# SP2.net
KiCad netlist of a schematic drawn in EAGLE
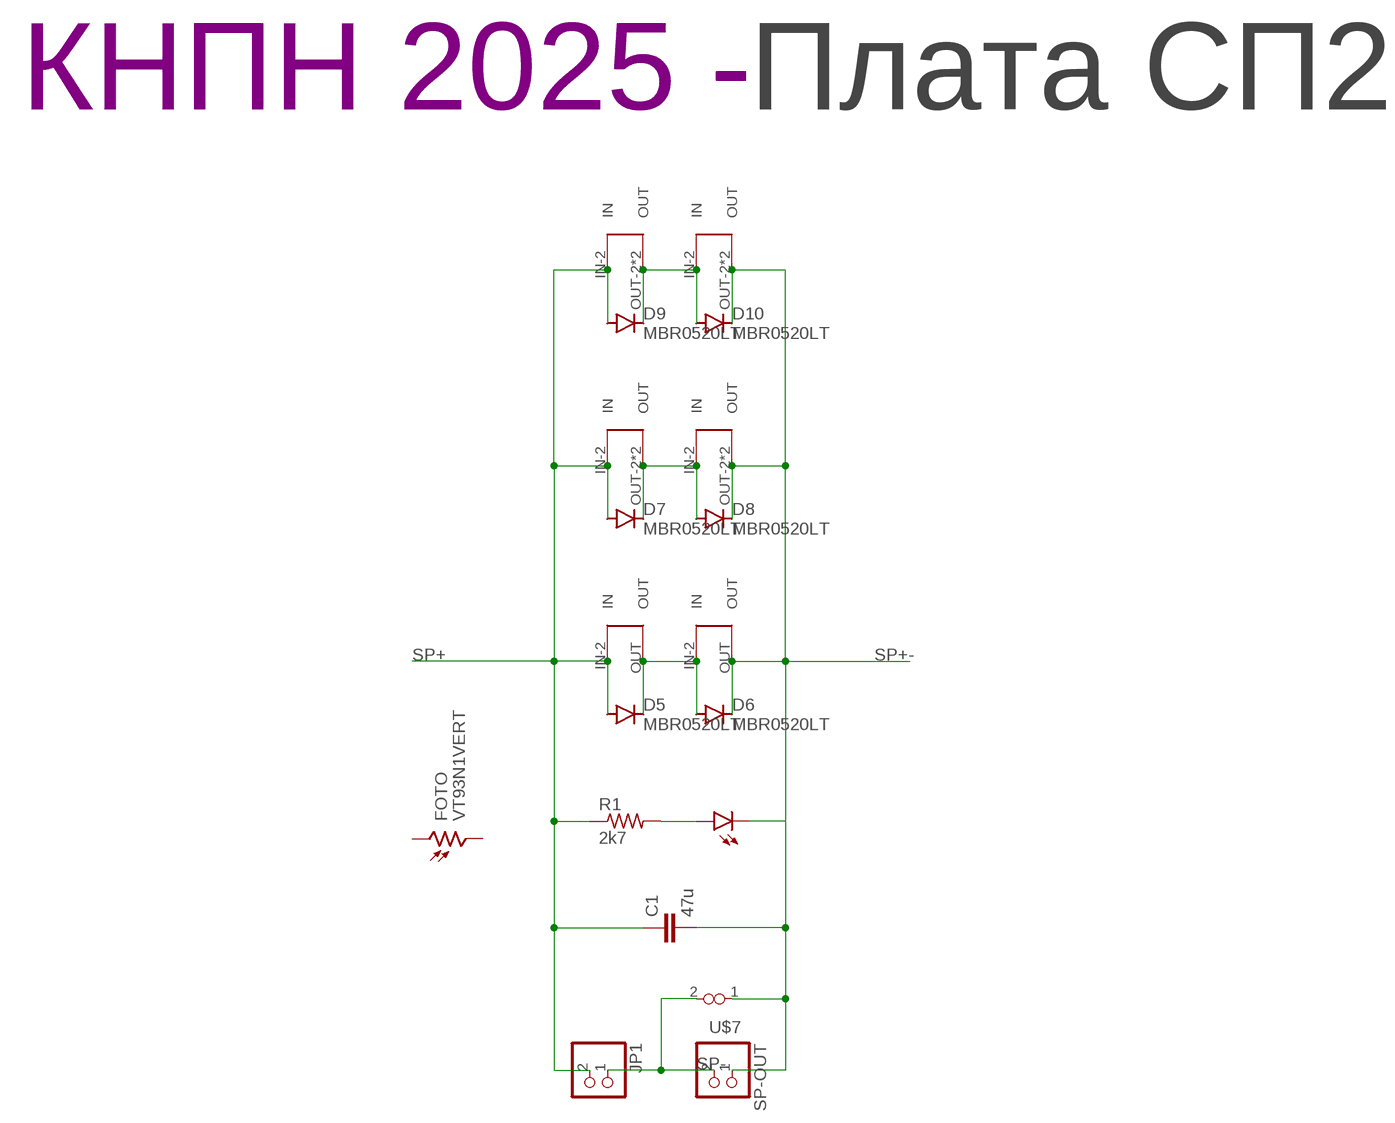
[diagram p0: schematic, sheet 1]

(export (version "E")
  (design (tool "Eeschema 10.0.6"))
  (components
    (comp (ref "C1")
      (value "47u")
      (footprint "eagle-import:C1210")
      (libsource (lib "eagle-import") (part "C-EUC1210"))
    )
    (comp (ref "D5")
      (value "MBR0520LT")
      (footprint "eagle-import:SOD123")
      (libsource (lib "eagle-import") (part "MBR0520LT"))
    )
    (comp (ref "D6")
      (value "MBR0520LT")
      (footprint "eagle-import:SOD123")
      (libsource (lib "eagle-import") (part "MBR0520LT"))
    )
    (comp (ref "D7")
      (value "MBR0520LT")
      (footprint "eagle-import:SOD123")
      (libsource (lib "eagle-import") (part "MBR0520LT"))
    )
    (comp (ref "D8")
      (value "MBR0520LT")
      (footprint "eagle-import:SOD123")
      (libsource (lib "eagle-import") (part "MBR0520LT"))
    )
    (comp (ref "D9")
      (value "MBR0520LT")
      (footprint "eagle-import:SOD123")
      (libsource (lib "eagle-import") (part "MBR0520LT"))
    )
    (comp (ref "D10")
      (value "MBR0520LT")
      (footprint "eagle-import:SOD123")
      (libsource (lib "eagle-import") (part "MBR0520LT"))
    )
    (comp (ref "FOTO")
      (value "VT93N1VERT")
      (footprint "eagle-import:VT93N1-VERT")
      (libsource (lib "eagle-import") (part "VT93N1VERT"))
    )
    (comp (ref "JP1")
      (value "PINHD-1X2")
      (footprint "eagle-import:1X02")
      (libsource (lib "eagle-import") (part "PINHD-1X2"))
    )
    (comp (ref "PWR")
      (value "LEDCHIP-LED0603")
      (footprint "eagle-import:CHIP-LED0603")
      (libsource (lib "eagle-import") (part "LEDCHIP-LED0603"))
    )
    (comp (ref "R1")
      (value "2k7")
      (footprint "eagle-import:R0603")
      (libsource (lib "eagle-import") (part "R-US_R0603"))
    )
    (comp (ref "SP-OUT")
      (value "PINHD-1X2")
      (footprint "eagle-import:1X02")
      (libsource (lib "eagle-import") (part "PINHD-1X2"))
    )
    (comp (ref "U$1")
      (value "Плата СП2")
      (footprint "eagle-import:LOGO")
      (libsource (lib "eagle-import") (part "LOGOPCB-{dblquote}{dblquote}"))
    )
    (comp (ref "U$5")
      (value "SOLAR-2_1")
      (footprint "eagle-import:SOLAR_1-2")
      (libsource (lib "eagle-import") (part "SOLAR-2_1"))
    )
    (comp (ref "U$6")
      (value "SOLAR-2_1")
      (footprint "eagle-import:SOLAR_1-2")
      (libsource (lib "eagle-import") (part "SOLAR-2_1"))
    )
    (comp (ref "U$7")
      (value "VIAS-CONNECT")
      (footprint "eagle-import:VIAS-CONNECT")
      (libsource (lib "eagle-import") (part "VIAS-CONNECT"))
    )
    (comp (ref "U$8")
      (value "SOLAR-2_0")
      (footprint "eagle-import:SOLAR_0-2")
      (libsource (lib "eagle-import") (part "SOLAR-2_0"))
    )
    (comp (ref "U$9")
      (value "SOLAR-2_0")
      (footprint "eagle-import:SOLAR_0-2")
      (libsource (lib "eagle-import") (part "SOLAR-2_0"))
    )
    (comp (ref "U$10")
      (value "SOLAR-2_0")
      (footprint "eagle-import:SOLAR_0-2")
      (libsource (lib "eagle-import") (part "SOLAR-2_0"))
    )
    (comp (ref "U$11")
      (value "SOLAR-2_0")
      (footprint "eagle-import:SOLAR_0-2")
      (libsource (lib "eagle-import") (part "SOLAR-2_0"))
    )
  )
  (nets
    (net (code "1") (name "/SP+") (class "Default")
      (node (ref "C1") (pin "1") (pinfunction "1_1") (pintype "passive"))
      (node (ref "D5") (pin "A") (pinfunction "A_A") (pintype "passive"))
      (node (ref "D7") (pin "A") (pinfunction "A_A") (pintype "passive"))
      (node (ref "D9") (pin "A") (pinfunction "A_A") (pintype "passive"))
      (node (ref "JP1") (pin "2") (pinfunction "2_2") (pintype "passive"))
      (node (ref "R1") (pin "1") (pinfunction "1_1") (pintype "passive"))
      (node (ref "U$10") (pin "IN-2") (pinfunction "IN_IN-2") (pintype "bidirectional"))
      (node (ref "U$5") (pin "IN-2") (pinfunction "IN_IN-2") (pintype "bidirectional"))
      (node (ref "U$8") (pin "IN-2") (pinfunction "IN_IN-2") (pintype "bidirectional"))
    )
    (net (code "2") (name "/SP+-") (class "Default")
      (node (ref "C1") (pin "2") (pinfunction "2_2") (pintype "passive"))
      (node (ref "D10") (pin "C") (pinfunction "C_C") (pintype "passive"))
      (node (ref "D6") (pin "C") (pinfunction "C_C") (pintype "passive"))
      (node (ref "D8") (pin "C") (pinfunction "C_C") (pintype "passive"))
      (node (ref "PWR") (pin "C") (pinfunction "C_C") (pintype "passive"))
      (node (ref "SP-OUT") (pin "1") (pinfunction "1_1") (pintype "passive"))
      (node (ref "U$11") (pin "OUT-2") (pinfunction "OUT_OUT-2") (pintype "bidirectional"))
      (node (ref "U$11") (pin "OUT-21") (pinfunction "OUT_OUT-21") (pintype "bidirectional"))
      (node (ref "U$6") (pin "OUT") (pinfunction "OUT_OUT") (pintype "bidirectional"))
      (node (ref "U$7") (pin "1") (pinfunction "1_1") (pintype "passive"))
      (node (ref "U$9") (pin "OUT-2") (pinfunction "OUT_OUT-2") (pintype "bidirectional"))
      (node (ref "U$9") (pin "OUT-21") (pinfunction "OUT_OUT-21") (pintype "bidirectional"))
    )
    (net (code "3") (name "/SP-") (class "Default")
      (node (ref "JP1") (pin "1") (pinfunction "1_1") (pintype "passive"))
      (node (ref "SP-OUT") (pin "2") (pinfunction "2_2") (pintype "passive"))
      (node (ref "U$7") (pin "2") (pinfunction "2_2") (pintype "passive"))
    )
    (net (code "4") (name "Net-(PWR-PadA)") (class "Default")
      (node (ref "PWR") (pin "A") (pinfunction "A_A") (pintype "passive"))
      (node (ref "R1") (pin "2") (pinfunction "2_2") (pintype "passive"))
    )
    (net (code "5") (name "Net-(U$6-IN)") (class "Default")
      (node (ref "D5") (pin "C") (pinfunction "C_C") (pintype "passive"))
      (node (ref "D6") (pin "A") (pinfunction "A_A") (pintype "passive"))
      (node (ref "U$5") (pin "OUT") (pinfunction "OUT_OUT") (pintype "bidirectional"))
      (node (ref "U$6") (pin "IN-2") (pinfunction "IN_IN-2") (pintype "bidirectional"))
    )
    (net (code "6") (name "Net-(U$9-IN)") (class "Default")
      (node (ref "D7") (pin "C") (pinfunction "C_C") (pintype "passive"))
      (node (ref "D8") (pin "A") (pinfunction "A_A") (pintype "passive"))
      (node (ref "U$8") (pin "OUT-2") (pinfunction "OUT_OUT-2") (pintype "bidirectional"))
      (node (ref "U$8") (pin "OUT-21") (pinfunction "OUT_OUT-21") (pintype "bidirectional"))
      (node (ref "U$9") (pin "IN-2") (pinfunction "IN_IN-2") (pintype "bidirectional"))
    )
    (net (code "7") (name "Net-(U$11-IN)") (class "Default")
      (node (ref "D10") (pin "A") (pinfunction "A_A") (pintype "passive"))
      (node (ref "D9") (pin "C") (pinfunction "C_C") (pintype "passive"))
      (node (ref "U$10") (pin "OUT-2") (pinfunction "OUT_OUT-2") (pintype "bidirectional"))
      (node (ref "U$10") (pin "OUT-21") (pinfunction "OUT_OUT-21") (pintype "bidirectional"))
      (node (ref "U$11") (pin "IN-2") (pinfunction "IN_IN-2") (pintype "bidirectional"))
    )
    (net (code "8") (name "unconnected-(FOTO-1-PadP$1)") (class "Default")
      (node (ref "FOTO") (pin "P$1") (pinfunction "1_P$1") (pintype "passive"))
    )
    (net (code "9") (name "unconnected-(FOTO-2-PadP$2)") (class "Default")
      (node (ref "FOTO") (pin "P$2") (pinfunction "2_P$2") (pintype "passive"))
    )
  )
)
